# eeprom_adapter.net
KiCad netlist of a schematic drawn in EAGLE
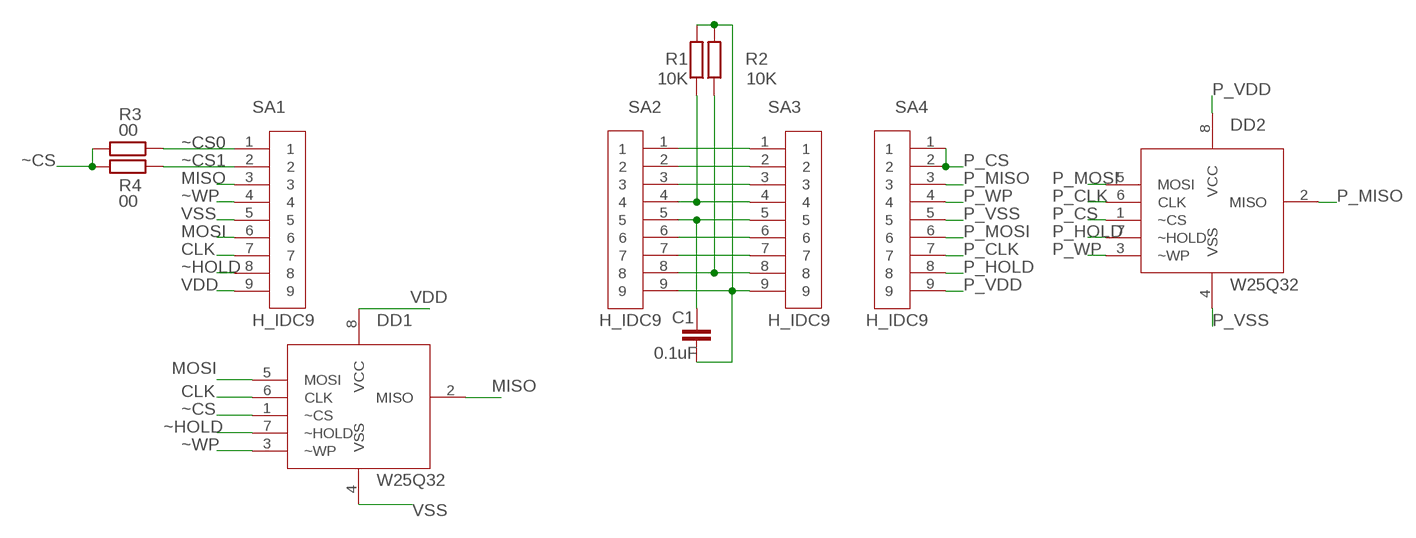
[diagram p0: schematic, sheet 1]

(export (version "E")
  (design (tool "Eeschema 10.0.6"))
  (components
    (comp (ref "C1")
      (value "0.1uF")
      (footprint "eagle-import:C0603")
      (libsource (lib "eagle-import") (part "C-EUC0603"))
    )
    (comp (ref "DD1")
      (value "W25Q32")
      (footprint "eagle-import:SOIC-208")
      (libsource (lib "eagle-import") (part "W25Q32SOIC208"))
    )
    (comp (ref "DD2")
      (value "W25Q32")
      (footprint "eagle-import:H_DIL08")
      (libsource (lib "eagle-import") (part "W25Q32H_DIP8"))
    )
    (comp (ref "R1")
      (value "10K")
      (footprint "eagle-import:R0603")
      (libsource (lib "eagle-import") (part "R-EU_R0603"))
    )
    (comp (ref "R2")
      (value "10K")
      (footprint "eagle-import:R0603")
      (libsource (lib "eagle-import") (part "R-EU_R0603"))
    )
    (comp (ref "R3")
      (value "00")
      (footprint "eagle-import:R0603")
      (libsource (lib "eagle-import") (part "R-EU_R0603"))
    )
    (comp (ref "R4")
      (value "00")
      (footprint "eagle-import:R0603")
      (libsource (lib "eagle-import") (part "R-EU_R0603"))
    )
    (comp (ref "SA1")
      (value "H_IDC9")
      (footprint "eagle-import:H_IDC8X1_27")
      (libsource (lib "eagle-import") (part "H_IDC9"))
    )
    (comp (ref "SA2")
      (value "H_IDC9")
      (footprint "eagle-import:H_IDC8X1_27")
      (libsource (lib "eagle-import") (part "H_IDC9"))
    )
    (comp (ref "SA3")
      (value "H_IDC9")
      (footprint "eagle-import:H_IDC8X1_27")
      (libsource (lib "eagle-import") (part "H_IDC9"))
    )
    (comp (ref "SA4")
      (value "H_IDC9")
      (footprint "eagle-import:H_IDC8X1_27")
      (libsource (lib "eagle-import") (part "H_IDC9"))
    )
  )
  (nets
    (net (code "1") (name "/CLK") (class "Default")
      (node (ref "DD1") (pin "6") (pinfunction "CLK_6") (pintype "input"))
      (node (ref "SA1") (pin "7") (pinfunction "7_7") (pintype "bidirectional"))
    )
    (net (code "2") (name "/MISO") (class "Default")
      (node (ref "DD1") (pin "2") (pinfunction "MISO_2") (pintype "bidirectional"))
      (node (ref "SA1") (pin "3") (pinfunction "3_3") (pintype "bidirectional"))
    )
    (net (code "3") (name "/MOSI") (class "Default")
      (node (ref "DD1") (pin "5") (pinfunction "MOSI_5") (pintype "bidirectional"))
      (node (ref "SA1") (pin "6") (pinfunction "6_6") (pintype "bidirectional"))
    )
    (net (code "4") (name "/P_CLK") (class "Default")
      (node (ref "DD2") (pin "6") (pinfunction "CLK_6") (pintype "input"))
      (node (ref "SA4") (pin "7") (pinfunction "7_7") (pintype "bidirectional"))
    )
    (net (code "5") (name "/P_CS") (class "Default")
      (node (ref "DD2") (pin "1") (pinfunction "~{CS}_1") (pintype "input"))
      (node (ref "SA4") (pin "1") (pinfunction "1_1") (pintype "bidirectional"))
      (node (ref "SA4") (pin "2") (pinfunction "2_2") (pintype "bidirectional"))
    )
    (net (code "6") (name "/P_HOLD") (class "Default")
      (node (ref "DD2") (pin "7") (pinfunction "~{HOLD}_7") (pintype "bidirectional"))
      (node (ref "SA4") (pin "8") (pinfunction "8_8") (pintype "bidirectional"))
    )
    (net (code "7") (name "/P_MISO") (class "Default")
      (node (ref "DD2") (pin "2") (pinfunction "MISO_2") (pintype "bidirectional"))
      (node (ref "SA4") (pin "3") (pinfunction "3_3") (pintype "bidirectional"))
    )
    (net (code "8") (name "/P_MOSI") (class "Default")
      (node (ref "DD2") (pin "5") (pinfunction "MOSI_5") (pintype "bidirectional"))
      (node (ref "SA4") (pin "6") (pinfunction "6_6") (pintype "bidirectional"))
    )
    (net (code "9") (name "/P_VDD") (class "Default")
      (node (ref "DD2") (pin "8") (pinfunction "VCC_8") (pintype "power_in"))
      (node (ref "SA4") (pin "9") (pinfunction "9_9") (pintype "bidirectional"))
    )
    (net (code "10") (name "/P_VSS") (class "Default")
      (node (ref "DD2") (pin "4") (pinfunction "VSS_4") (pintype "power_in"))
      (node (ref "SA4") (pin "5") (pinfunction "5_5") (pintype "bidirectional"))
    )
    (net (code "11") (name "/P_WP") (class "Default")
      (node (ref "DD2") (pin "3") (pinfunction "~{WP}_3") (pintype "input"))
      (node (ref "SA4") (pin "4") (pinfunction "4_4") (pintype "bidirectional"))
    )
    (net (code "12") (name "/VDD") (class "Default")
      (node (ref "DD1") (pin "8") (pinfunction "VCC_8") (pintype "power_in"))
      (node (ref "SA1") (pin "9") (pinfunction "9_9") (pintype "bidirectional"))
    )
    (net (code "13") (name "/VSS") (class "Default")
      (node (ref "DD1") (pin "4") (pinfunction "VSS_4") (pintype "power_in"))
      (node (ref "SA1") (pin "5") (pinfunction "5_5") (pintype "bidirectional"))
    )
    (net (code "14") (name "/~{CS0}") (class "Default")
      (node (ref "R3") (pin "1") (pinfunction "1_1") (pintype "passive"))
      (node (ref "SA1") (pin "1") (pinfunction "1_1") (pintype "bidirectional"))
    )
    (net (code "15") (name "/~{CS1}") (class "Default")
      (node (ref "R4") (pin "1") (pinfunction "1_1") (pintype "passive"))
      (node (ref "SA1") (pin "2") (pinfunction "2_2") (pintype "bidirectional"))
    )
    (net (code "16") (name "/~{CS}") (class "Default")
      (node (ref "DD1") (pin "1") (pinfunction "~{CS}_1") (pintype "input"))
      (node (ref "R3") (pin "2") (pinfunction "2_2") (pintype "passive"))
      (node (ref "R4") (pin "2") (pinfunction "2_2") (pintype "passive"))
    )
    (net (code "17") (name "/~{HOLD}") (class "Default")
      (node (ref "DD1") (pin "7") (pinfunction "~{HOLD}_7") (pintype "bidirectional"))
      (node (ref "SA1") (pin "8") (pinfunction "8_8") (pintype "bidirectional"))
    )
    (net (code "18") (name "/~{WP}") (class "Default")
      (node (ref "DD1") (pin "3") (pinfunction "~{WP}_3") (pintype "input"))
      (node (ref "SA1") (pin "4") (pinfunction "4_4") (pintype "bidirectional"))
    )
    (net (code "19") (name "Net-(C1-Pad1)") (class "Default")
      (node (ref "C1") (pin "1") (pinfunction "1_1") (pintype "passive"))
      (node (ref "SA2") (pin "5") (pinfunction "5_5") (pintype "bidirectional"))
      (node (ref "SA3") (pin "5") (pinfunction "5_5") (pintype "bidirectional"))
    )
    (net (code "20") (name "Net-(C1-Pad2)") (class "Default")
      (node (ref "C1") (pin "2") (pinfunction "2_2") (pintype "passive"))
      (node (ref "R1") (pin "2") (pinfunction "2_2") (pintype "passive"))
      (node (ref "R2") (pin "2") (pinfunction "2_2") (pintype "passive"))
      (node (ref "SA2") (pin "9") (pinfunction "9_9") (pintype "bidirectional"))
      (node (ref "SA3") (pin "9") (pinfunction "9_9") (pintype "bidirectional"))
    )
    (net (code "21") (name "Net-(R1-Pad1)") (class "Default")
      (node (ref "R1") (pin "1") (pinfunction "1_1") (pintype "passive"))
      (node (ref "SA2") (pin "4") (pinfunction "4_4") (pintype "bidirectional"))
      (node (ref "SA3") (pin "4") (pinfunction "4_4") (pintype "bidirectional"))
    )
    (net (code "22") (name "Net-(R2-Pad1)") (class "Default")
      (node (ref "R2") (pin "1") (pinfunction "1_1") (pintype "passive"))
      (node (ref "SA2") (pin "8") (pinfunction "8_8") (pintype "bidirectional"))
      (node (ref "SA3") (pin "8") (pinfunction "8_8") (pintype "bidirectional"))
    )
    (net (code "23") (name "Net-(SA2-Pad1)") (class "Default")
      (node (ref "SA2") (pin "1") (pinfunction "1_1") (pintype "bidirectional"))
      (node (ref "SA3") (pin "1") (pinfunction "1_1") (pintype "bidirectional"))
    )
    (net (code "24") (name "Net-(SA2-Pad2)") (class "Default")
      (node (ref "SA2") (pin "2") (pinfunction "2_2") (pintype "bidirectional"))
      (node (ref "SA3") (pin "2") (pinfunction "2_2") (pintype "bidirectional"))
    )
    (net (code "25") (name "Net-(SA2-Pad3)") (class "Default")
      (node (ref "SA2") (pin "3") (pinfunction "3_3") (pintype "bidirectional"))
      (node (ref "SA3") (pin "3") (pinfunction "3_3") (pintype "bidirectional"))
    )
    (net (code "26") (name "Net-(SA2-Pad6)") (class "Default")
      (node (ref "SA2") (pin "6") (pinfunction "6_6") (pintype "bidirectional"))
      (node (ref "SA3") (pin "6") (pinfunction "6_6") (pintype "bidirectional"))
    )
    (net (code "27") (name "Net-(SA2-Pad7)") (class "Default")
      (node (ref "SA2") (pin "7") (pinfunction "7_7") (pintype "bidirectional"))
      (node (ref "SA3") (pin "7") (pinfunction "7_7") (pintype "bidirectional"))
    )
  )
)
